# roco1044.net
KiCad netlist of a schematic drawn in EAGLE
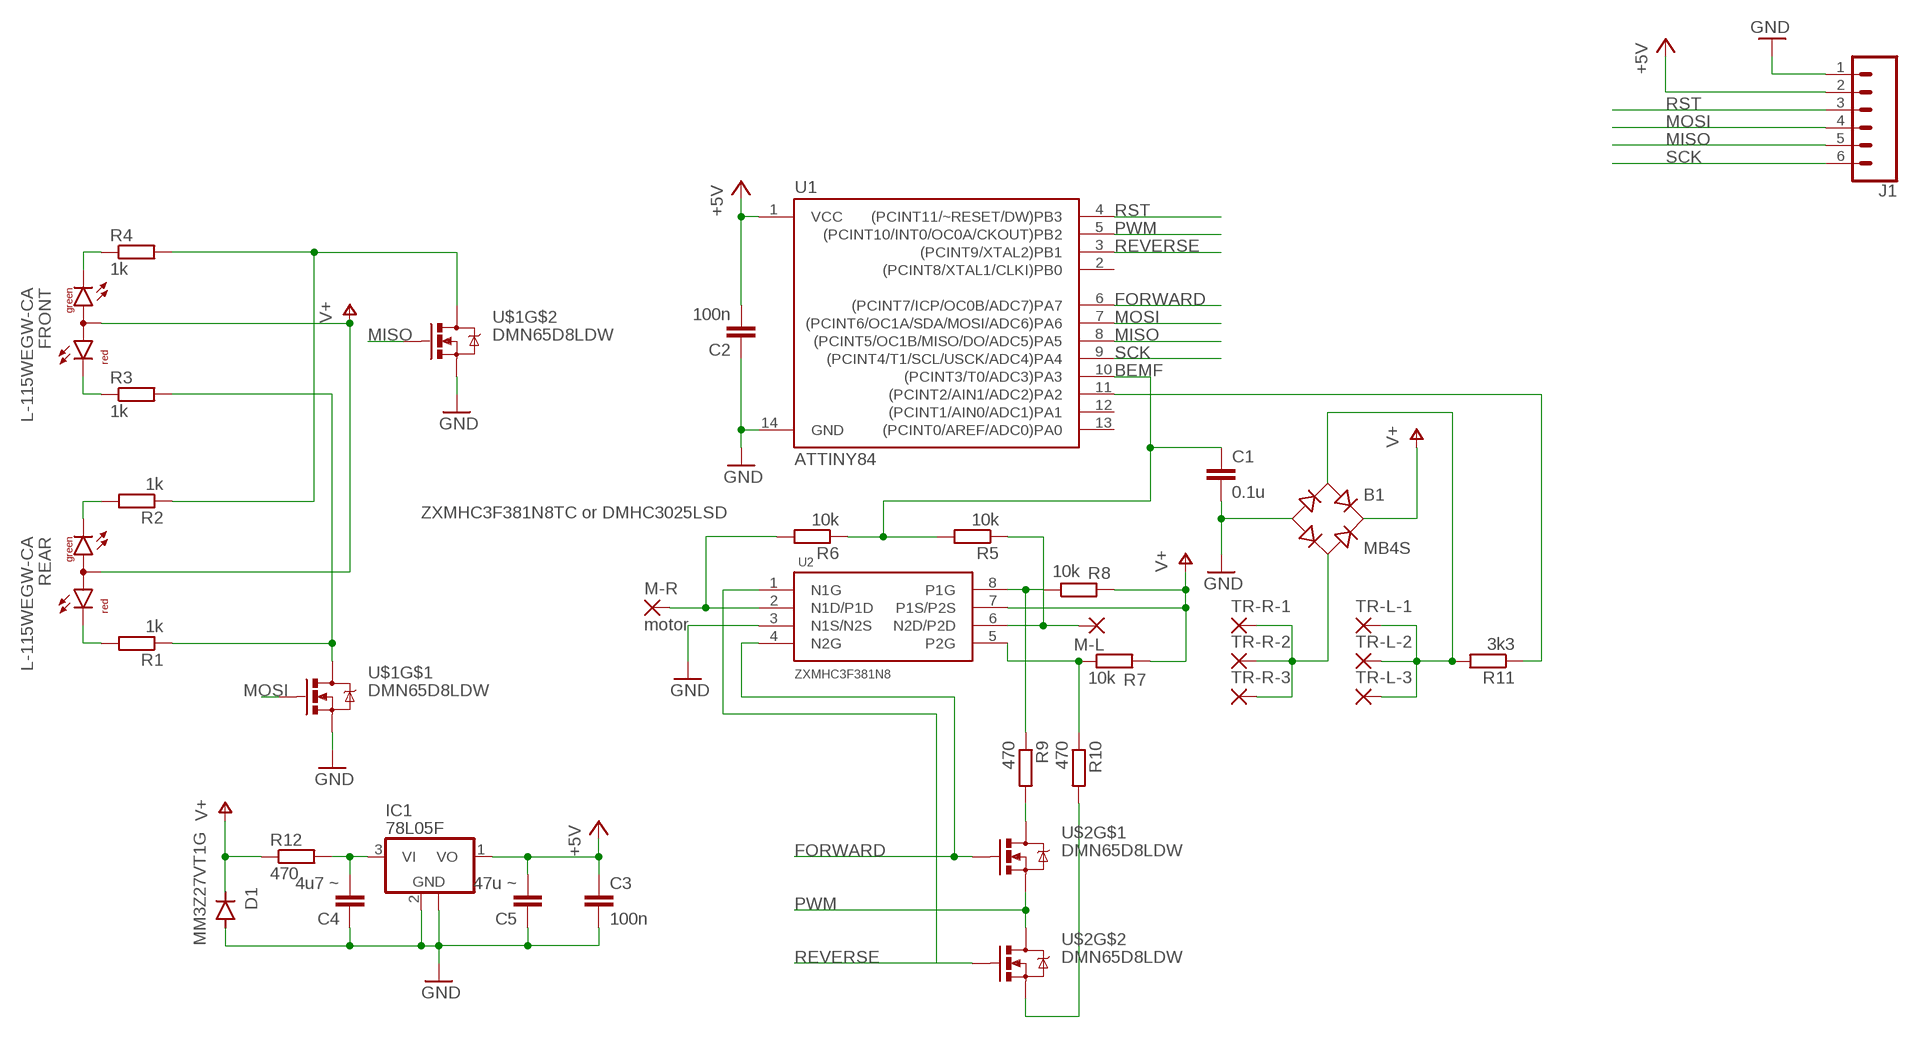
[diagram p0: schematic, sheet 1]

(export (version "E")
  (design (tool "Eeschema 10.0.6"))
  (components
    (comp (ref "B1")
      (value "MB4S")
      (footprint "eagle-import:SOIC-4")
      (libsource (lib "eagle-import") (part "MBS4"))
    )
    (comp (ref "C1")
      (value "0.1u")
      (footprint "eagle-import:C0805")
      (libsource (lib "eagle-import") (part "resistor_348_C-EUC0805"))
    )
    (comp (ref "C2")
      (value "100n")
      (footprint "eagle-import:C1210")
      (libsource (lib "eagle-import") (part "C-EUC1210"))
    )
    (comp (ref "C3")
      (value "100n")
      (footprint "eagle-import:C1210")
      (libsource (lib "eagle-import") (part "C-EUC1210"))
    )
    (comp (ref "C4")
      (value "4u7 ~")
      (footprint "eagle-import:C3216")
      (libsource (lib "eagle-import") (part "C-EUC3216"))
    )
    (comp (ref "C5")
      (value "47u ~")
      (footprint "eagle-import:C3216")
      (libsource (lib "eagle-import") (part "C-EUC3216"))
    )
    (comp (ref "D1")
      (value "MM3Z27VT1G")
      (footprint "eagle-import:SOD323-R")
      (libsource (lib "eagle-import") (part "DIODE-SOD323-R"))
    )
    (comp (ref "FRONT")
      (value "L-115WEGW-CA")
      (footprint "eagle-import:DUOLED-A-3MM")
      (libsource (lib "eagle-import") (part "L-115WEGW-CA"))
    )
    (comp (ref "IC1")
      (value "78L05F")
      (footprint "eagle-import:SOT89")
      (libsource (lib "eagle-import") (part "78LF05"))
    )
    (comp (ref "J1")
      (value "CONN_061.27MM")
      (footprint "eagle-import:1X06_1.27MM")
      (libsource (lib "eagle-import") (part "CONN_061.27MM"))
    )
    (comp (ref "M-L")
      (value "SMD5")
      (footprint "eagle-import:SMD2,54-5,08")
      (libsource (lib "eagle-import") (part "SMD5"))
    )
    (comp (ref "M-R")
      (value "motor")
      (footprint "eagle-import:SMD2,54-5,08")
      (libsource (lib "eagle-import") (part "SMD5"))
    )
    (comp (ref "R1")
      (value "1k")
      (footprint "eagle-import:R0805")
      (libsource (lib "eagle-import") (part "R-EU_R0805"))
    )
    (comp (ref "R2")
      (value "1k")
      (footprint "eagle-import:R0805")
      (libsource (lib "eagle-import") (part "R-EU_R0805"))
    )
    (comp (ref "R3")
      (value "1k")
      (footprint "eagle-import:R0805")
      (libsource (lib "eagle-import") (part "R-EU_R0805"))
    )
    (comp (ref "R4")
      (value "1k")
      (footprint "eagle-import:R0805")
      (libsource (lib "eagle-import") (part "R-EU_R0805"))
    )
    (comp (ref "R5")
      (value "10k")
      (footprint "eagle-import:R0805")
      (libsource (lib "eagle-import") (part "R-EU_R0805"))
    )
    (comp (ref "R6")
      (value "10k")
      (footprint "eagle-import:R0805")
      (libsource (lib "eagle-import") (part "R-EU_R0805"))
    )
    (comp (ref "R7")
      (value "10k")
      (footprint "eagle-import:R0805")
      (libsource (lib "eagle-import") (part "R-EU_R0805"))
    )
    (comp (ref "R8")
      (value "10k")
      (footprint "eagle-import:R0805")
      (libsource (lib "eagle-import") (part "R-EU_R0805"))
    )
    (comp (ref "R9")
      (value "470")
      (footprint "eagle-import:R0805")
      (libsource (lib "eagle-import") (part "R-EU_R0805"))
    )
    (comp (ref "R10")
      (value "470")
      (footprint "eagle-import:R0805")
      (libsource (lib "eagle-import") (part "R-EU_R0805"))
    )
    (comp (ref "R11")
      (value "3k3")
      (footprint "eagle-import:R0805")
      (libsource (lib "eagle-import") (part "R-EU_R0805"))
    )
    (comp (ref "R12")
      (value "470")
      (footprint "eagle-import:R0805")
      (libsource (lib "eagle-import") (part "R-EU_R0805"))
    )
    (comp (ref "REAR")
      (value "L-115WEGW-CA")
      (footprint "eagle-import:DUOLED-A-3MM")
      (libsource (lib "eagle-import") (part "L-115WEGW-CA"))
    )
    (comp (ref "TR-L-1")
      (value "SMD5")
      (footprint "eagle-import:SMD2,54-5,08")
      (libsource (lib "eagle-import") (part "SMD5"))
    )
    (comp (ref "TR-L-2")
      (value "SMD5")
      (footprint "eagle-import:SMD2,54-5,08")
      (libsource (lib "eagle-import") (part "SMD5"))
    )
    (comp (ref "TR-L-3")
      (value "SMD5")
      (footprint "eagle-import:SMD2,54-5,08")
      (libsource (lib "eagle-import") (part "SMD5"))
    )
    (comp (ref "TR-R-1")
      (value "SMD5")
      (footprint "eagle-import:SMD2,54-5,08")
      (libsource (lib "eagle-import") (part "SMD5"))
    )
    (comp (ref "TR-R-2")
      (value "SMD5")
      (footprint "eagle-import:SMD2,54-5,08")
      (libsource (lib "eagle-import") (part "SMD5"))
    )
    (comp (ref "TR-R-3")
      (value "SMD5")
      (footprint "eagle-import:SMD2,54-5,08")
      (libsource (lib "eagle-import") (part "SMD5"))
    )
    (comp (ref "U$1")
      (value "DMN65D8LDW")
      (footprint "eagle-import:SOT363")
      (libsource (lib "eagle-import") (part "DMN65D8LDW"))
    )
    (comp (ref "U$2")
      (value "DMN65D8LDW")
      (footprint "eagle-import:SOT363")
      (libsource (lib "eagle-import") (part "DMN65D8LDW"))
    )
    (comp (ref "U1")
      (value "ATTINY84")
      (footprint "eagle-import:SO14")
      (libsource (lib "eagle-import") (part "ATTINY84"))
    )
    (comp (ref "U2")
      (value "ZXMHC3F381N8")
      (footprint "eagle-import:SOIC8")
      (libsource (lib "eagle-import") (part "ZXMHC3F381N8"))
    )
  )
  (nets
    (net (code "1") (name "+5V") (class "Default")
      (node (ref "C2") (pin "2") (pinfunction "2_2") (pintype "passive"))
      (node (ref "C3") (pin "1") (pinfunction "1_1") (pintype "passive"))
      (node (ref "C5") (pin "2") (pinfunction "2_2") (pintype "passive"))
      (node (ref "IC1") (pin "1") (pinfunction "VO_1") (pintype "passive"))
      (node (ref "J1") (pin "2") (pinfunction "2_2") (pintype "passive"))
      (node (ref "U1") (pin "1") (pinfunction "VCC_1") (pintype "bidirectional"))
    )
    (net (code "2") (name "/BEMF") (class "Default")
      (node (ref "C1") (pin "1") (pinfunction "1_1") (pintype "passive"))
      (node (ref "R5") (pin "2") (pinfunction "2_2") (pintype "passive"))
      (node (ref "R6") (pin "1") (pinfunction "1_1") (pintype "passive"))
      (node (ref "U1") (pin "10") (pinfunction "(PCINT3/T0/ADC3)PA3_10") (pintype "bidirectional"))
    )
    (net (code "3") (name "/FORWARD") (class "Default")
      (node (ref "U$2") (pin "P$2") (pinfunction "G_P$2") (pintype "passive"))
      (node (ref "U1") (pin "6") (pinfunction "(PCINT7/ICP/OC0B/ADC7)PA7_6") (pintype "bidirectional"))
      (node (ref "U2") (pin "4") (pinfunction "N2G_4") (pintype "bidirectional"))
    )
    (net (code "4") (name "/MISO") (class "Default")
      (node (ref "J1") (pin "5") (pinfunction "5_5") (pintype "passive"))
      (node (ref "U$1") (pin "P$5") (pinfunction "G_P$5") (pintype "passive"))
      (node (ref "U1") (pin "8") (pinfunction "(PCINT5/OC1B/MISO/DO/ADC5)PA5_8") (pintype "bidirectional"))
    )
    (net (code "5") (name "/MOSI") (class "Default")
      (node (ref "J1") (pin "4") (pinfunction "4_4") (pintype "passive"))
      (node (ref "U$1") (pin "P$2") (pinfunction "G_P$2") (pintype "passive"))
      (node (ref "U1") (pin "7") (pinfunction "(PCINT6/OC1A/SDA/MOSI/ADC6)PA6_7") (pintype "bidirectional"))
    )
    (net (code "6") (name "/PWM") (class "Default")
      (node (ref "U$2") (pin "P$1") (pinfunction "D_P$1") (pintype "passive"))
      (node (ref "U$2") (pin "P$3") (pinfunction "S_P$3") (pintype "passive"))
      (node (ref "U1") (pin "5") (pinfunction "(PCINT10/INT0/OC0A/CKOUT)PB2_5") (pintype "bidirectional"))
    )
    (net (code "7") (name "/REVERSE") (class "Default")
      (node (ref "U$2") (pin "P$5") (pinfunction "G_P$5") (pintype "passive"))
      (node (ref "U1") (pin "3") (pinfunction "(PCINT9/XTAL2)PB1_3") (pintype "bidirectional"))
      (node (ref "U2") (pin "1") (pinfunction "N1G_1") (pintype "bidirectional"))
    )
    (net (code "8") (name "/RST") (class "Default")
      (node (ref "J1") (pin "3") (pinfunction "3_3") (pintype "passive"))
      (node (ref "U1") (pin "4") (pinfunction "(PCINT11/~{RESET/DW})PB3_4") (pintype "bidirectional"))
    )
    (net (code "9") (name "/SCK") (class "Default")
      (node (ref "J1") (pin "6") (pinfunction "6_6") (pintype "passive"))
      (node (ref "U1") (pin "9") (pinfunction "(PCINT4/T1/SCL/USCK/ADC4)PA4_9") (pintype "bidirectional"))
    )
    (net (code "10") (name "GND") (class "Default")
      (node (ref "B1") (pin "-") (pinfunction "-_-") (pintype "passive"))
      (node (ref "C1") (pin "2") (pinfunction "2_2") (pintype "passive"))
      (node (ref "C2") (pin "1") (pinfunction "1_1") (pintype "passive"))
      (node (ref "C3") (pin "2") (pinfunction "2_2") (pintype "passive"))
      (node (ref "C4") (pin "1") (pinfunction "1_1") (pintype "passive"))
      (node (ref "C5") (pin "1") (pinfunction "1_1") (pintype "passive"))
      (node (ref "D1") (pin "A") (pinfunction "A_A") (pintype "passive"))
      (node (ref "IC1") (pin "2") (pinfunction "GND_2") (pintype "passive"))
      (node (ref "IC1") (pin "2@1") (pinfunction "GND_2@1") (pintype "passive"))
      (node (ref "J1") (pin "1") (pinfunction "1_1") (pintype "passive"))
      (node (ref "U$1") (pin "P$3") (pinfunction "S_P$3") (pintype "passive"))
      (node (ref "U$1") (pin "P$6") (pinfunction "S_P$6") (pintype "passive"))
      (node (ref "U1") (pin "14") (pinfunction "GND_14") (pintype "bidirectional"))
      (node (ref "U2") (pin "3") (pinfunction "N1S/N2S_3") (pintype "bidirectional"))
    )
    (net (code "11") (name "Net-(B1-AC1)") (class "Default")
      (node (ref "B1") (pin "~1") (pinfunction "AC1_~1") (pintype "passive"))
      (node (ref "R11") (pin "2") (pinfunction "2_2") (pintype "passive"))
      (node (ref "TR-L-1") (pin "1") (pinfunction "P_1") (pintype "passive"))
      (node (ref "TR-L-2") (pin "1") (pinfunction "P_1") (pintype "passive"))
      (node (ref "TR-L-3") (pin "1") (pinfunction "P_1") (pintype "passive"))
    )
    (net (code "12") (name "Net-(B1-AC2)") (class "Default")
      (node (ref "B1") (pin "~2") (pinfunction "AC2_~2") (pintype "passive"))
      (node (ref "TR-R-1") (pin "1") (pinfunction "P_1") (pintype "passive"))
      (node (ref "TR-R-2") (pin "1") (pinfunction "P_1") (pintype "passive"))
      (node (ref "TR-R-3") (pin "1") (pinfunction "P_1") (pintype "passive"))
    )
    (net (code "13") (name "Net-(FRONT-CG)") (class "Default")
      (node (ref "FRONT") (pin "1") (pinfunction "CG_1") (pintype "passive"))
      (node (ref "R4") (pin "1") (pinfunction "1_1") (pintype "passive"))
    )
    (net (code "14") (name "Net-(FRONT-CR)") (class "Default")
      (node (ref "FRONT") (pin "3") (pinfunction "CR_3") (pintype "passive"))
      (node (ref "R3") (pin "1") (pinfunction "1_1") (pintype "passive"))
    )
    (net (code "15") (name "Net-(IC1-VI)") (class "Default")
      (node (ref "C4") (pin "2") (pinfunction "2_2") (pintype "passive"))
      (node (ref "IC1") (pin "3") (pinfunction "VI_3") (pintype "input"))
      (node (ref "R12") (pin "2") (pinfunction "2_2") (pintype "passive"))
    )
    (net (code "16") (name "Net-(M-L-P)") (class "Default")
      (node (ref "M-L") (pin "1") (pinfunction "P_1") (pintype "passive"))
      (node (ref "R5") (pin "1") (pinfunction "1_1") (pintype "passive"))
      (node (ref "U2") (pin "6") (pinfunction "N2D/P2D_6") (pintype "bidirectional"))
    )
    (net (code "17") (name "Net-(M-R-P)") (class "Default")
      (node (ref "M-R") (pin "1") (pinfunction "P_1") (pintype "passive"))
      (node (ref "R6") (pin "2") (pinfunction "2_2") (pintype "passive"))
      (node (ref "U2") (pin "2") (pinfunction "N1D/P1D_2") (pintype "bidirectional"))
    )
    (net (code "18") (name "Net-(REAR-CG)") (class "Default")
      (node (ref "R2") (pin "2") (pinfunction "2_2") (pintype "passive"))
      (node (ref "REAR") (pin "1") (pinfunction "CG_1") (pintype "passive"))
    )
    (net (code "19") (name "Net-(REAR-CR)") (class "Default")
      (node (ref "R1") (pin "2") (pinfunction "2_2") (pintype "passive"))
      (node (ref "REAR") (pin "3") (pinfunction "CR_3") (pintype "passive"))
    )
    (net (code "20") (name "Net-(U$1A-D)") (class "Default")
      (node (ref "R1") (pin "1") (pinfunction "1_1") (pintype "passive"))
      (node (ref "R3") (pin "2") (pinfunction "2_2") (pintype "passive"))
      (node (ref "U$1") (pin "P$4") (pinfunction "D_P$4") (pintype "passive"))
    )
    (net (code "21") (name "Net-(U$1B-D)") (class "Default")
      (node (ref "R2") (pin "1") (pinfunction "1_1") (pintype "passive"))
      (node (ref "R4") (pin "2") (pinfunction "2_2") (pintype "passive"))
      (node (ref "U$1") (pin "P$1") (pinfunction "D_P$1") (pintype "passive"))
    )
    (net (code "22") (name "Net-(U$2A-D)") (class "Default")
      (node (ref "R9") (pin "2") (pinfunction "2_2") (pintype "passive"))
      (node (ref "U$2") (pin "P$4") (pinfunction "D_P$4") (pintype "passive"))
    )
    (net (code "23") (name "Net-(U$2B-S)") (class "Default")
      (node (ref "R10") (pin "2") (pinfunction "2_2") (pintype "passive"))
      (node (ref "U$2") (pin "P$6") (pinfunction "S_P$6") (pintype "passive"))
    )
    (net (code "24") (name "Net-(U1-(PCINT2{slash}AIN1{slash}ADC2)PA2)") (class "Default")
      (node (ref "R11") (pin "1") (pinfunction "1_1") (pintype "passive"))
      (node (ref "U1") (pin "11") (pinfunction "(PCINT2/AIN1/ADC2)PA2_11") (pintype "bidirectional"))
    )
    (net (code "25") (name "Net-(U2-P1G)") (class "Default")
      (node (ref "R8") (pin "1") (pinfunction "1_1") (pintype "passive"))
      (node (ref "R9") (pin "1") (pinfunction "1_1") (pintype "passive"))
      (node (ref "U2") (pin "8") (pinfunction "P1G_8") (pintype "bidirectional"))
    )
    (net (code "26") (name "Net-(U2-P2G)") (class "Default")
      (node (ref "R10") (pin "1") (pinfunction "1_1") (pintype "passive"))
      (node (ref "R7") (pin "1") (pinfunction "1_1") (pintype "passive"))
      (node (ref "U2") (pin "5") (pinfunction "P2G_5") (pintype "bidirectional"))
    )
    (net (code "27") (name "V+") (class "Default")
      (node (ref "B1") (pin "+") (pinfunction "+_+") (pintype "passive"))
      (node (ref "D1") (pin "C") (pinfunction "C_C") (pintype "passive"))
      (node (ref "FRONT") (pin "2") (pinfunction "A_2") (pintype "passive"))
      (node (ref "R12") (pin "1") (pinfunction "1_1") (pintype "passive"))
      (node (ref "R7") (pin "2") (pinfunction "2_2") (pintype "passive"))
      (node (ref "R8") (pin "2") (pinfunction "2_2") (pintype "passive"))
      (node (ref "REAR") (pin "2") (pinfunction "A_2") (pintype "passive"))
      (node (ref "U2") (pin "7") (pinfunction "P1S/P2S_7") (pintype "bidirectional"))
    )
    (net (code "28") (name "unconnected-(U1-(PCINT0{slash}AREF{slash}ADC0)PA0-Pad13)") (class "Default")
      (node (ref "U1") (pin "13") (pinfunction "(PCINT0/AREF/ADC0)PA0_13") (pintype "bidirectional"))
    )
    (net (code "29") (name "unconnected-(U1-(PCINT1{slash}AIN0{slash}ADC1)PA1-Pad12)") (class "Default")
      (node (ref "U1") (pin "12") (pinfunction "(PCINT1/AIN0/ADC1)PA1_12") (pintype "bidirectional"))
    )
    (net (code "30") (name "unconnected-(U1-(PCINT8{slash}XTAL1{slash}CLKI)PB0-Pad2)") (class "Default")
      (node (ref "U1") (pin "2") (pinfunction "(PCINT8/XTAL1/CLKI)PB0_2") (pintype "bidirectional"))
    )
  )
)
